# GuardDog.net
KiCad netlist of a schematic drawn in EAGLE
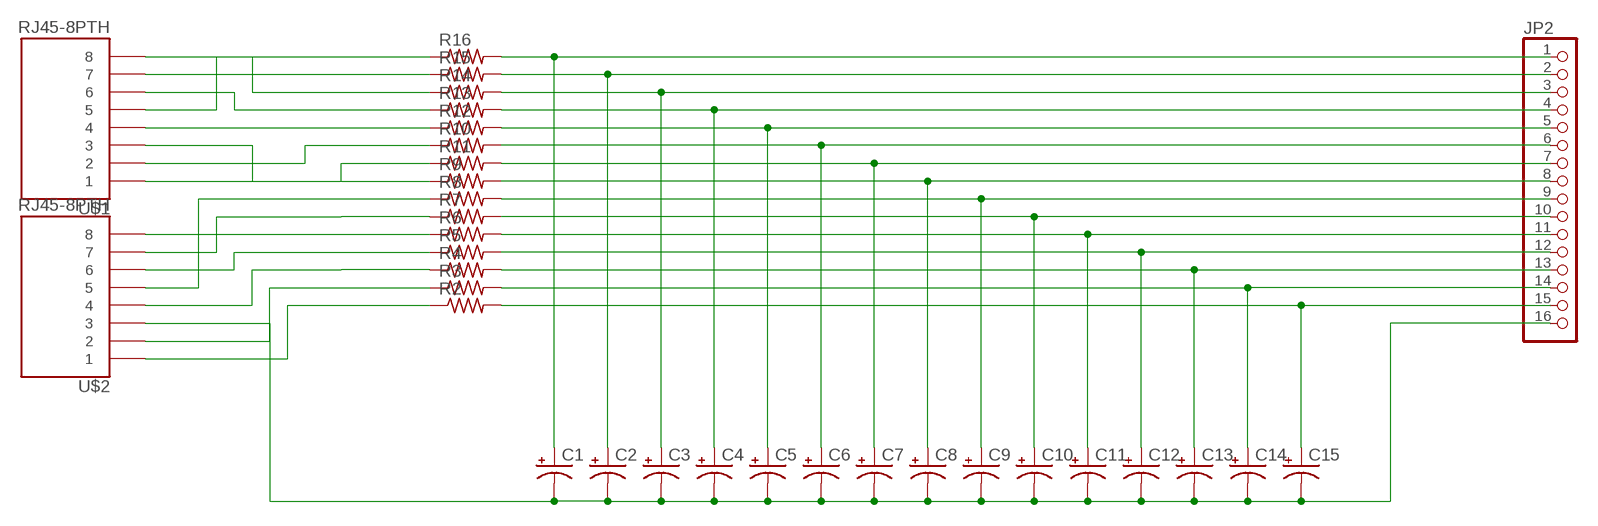
[diagram p0: schematic, sheet 1]

(export (version "E")
  (design (tool "Eeschema 10.0.6"))
  (components
    (comp (ref "C1")
      (value "CAP_POLPTH2")
      (footprint "eagle-import:CPOL-RADIAL-10UF-25V")
      (libsource (lib "eagle-import") (part "CAP_POLPTH2"))
    )
    (comp (ref "C2")
      (value "CAP_POLPTH2")
      (footprint "eagle-import:CPOL-RADIAL-10UF-25V")
      (libsource (lib "eagle-import") (part "CAP_POLPTH2"))
    )
    (comp (ref "C3")
      (value "CAP_POLPTH2")
      (footprint "eagle-import:CPOL-RADIAL-10UF-25V")
      (libsource (lib "eagle-import") (part "CAP_POLPTH2"))
    )
    (comp (ref "C4")
      (value "CAP_POLPTH2")
      (footprint "eagle-import:CPOL-RADIAL-10UF-25V")
      (libsource (lib "eagle-import") (part "CAP_POLPTH2"))
    )
    (comp (ref "C5")
      (value "CAP_POLPTH2")
      (footprint "eagle-import:CPOL-RADIAL-10UF-25V")
      (libsource (lib "eagle-import") (part "CAP_POLPTH2"))
    )
    (comp (ref "C6")
      (value "CAP_POLPTH2")
      (footprint "eagle-import:CPOL-RADIAL-10UF-25V")
      (libsource (lib "eagle-import") (part "CAP_POLPTH2"))
    )
    (comp (ref "C7")
      (value "CAP_POLPTH2")
      (footprint "eagle-import:CPOL-RADIAL-10UF-25V")
      (libsource (lib "eagle-import") (part "CAP_POLPTH2"))
    )
    (comp (ref "C8")
      (value "CAP_POLPTH2")
      (footprint "eagle-import:CPOL-RADIAL-10UF-25V")
      (libsource (lib "eagle-import") (part "CAP_POLPTH2"))
    )
    (comp (ref "C9")
      (value "CAP_POLPTH2")
      (footprint "eagle-import:CPOL-RADIAL-10UF-25V")
      (libsource (lib "eagle-import") (part "CAP_POLPTH2"))
    )
    (comp (ref "C10")
      (value "CAP_POLPTH2")
      (footprint "eagle-import:CPOL-RADIAL-10UF-25V")
      (libsource (lib "eagle-import") (part "CAP_POLPTH2"))
    )
    (comp (ref "C11")
      (value "CAP_POLPTH2")
      (footprint "eagle-import:CPOL-RADIAL-10UF-25V")
      (libsource (lib "eagle-import") (part "CAP_POLPTH2"))
    )
    (comp (ref "C12")
      (value "CAP_POLPTH2")
      (footprint "eagle-import:CPOL-RADIAL-10UF-25V")
      (libsource (lib "eagle-import") (part "CAP_POLPTH2"))
    )
    (comp (ref "C13")
      (value "CAP_POLPTH2")
      (footprint "eagle-import:CPOL-RADIAL-10UF-25V")
      (libsource (lib "eagle-import") (part "CAP_POLPTH2"))
    )
    (comp (ref "C14")
      (value "CAP_POLPTH2")
      (footprint "eagle-import:CPOL-RADIAL-10UF-25V")
      (libsource (lib "eagle-import") (part "CAP_POLPTH2"))
    )
    (comp (ref "C15")
      (value "CAP_POLPTH2")
      (footprint "eagle-import:CPOL-RADIAL-10UF-25V")
      (libsource (lib "eagle-import") (part "CAP_POLPTH2"))
    )
    (comp (ref "JP2")
      (value "PINHD-1X16")
      (footprint "eagle-import:1X16")
      (libsource (lib "eagle-import") (part "PINHD-1X16"))
    )
    (comp (ref "R2")
      (value "R-US_0204/5")
      (footprint "eagle-import:0204_5")
      (libsource (lib "eagle-import") (part "R-US_0204/5"))
    )
    (comp (ref "R3")
      (value "R-US_0204/5")
      (footprint "eagle-import:0204_5")
      (libsource (lib "eagle-import") (part "R-US_0204/5"))
    )
    (comp (ref "R4")
      (value "R-US_0204/5")
      (footprint "eagle-import:0204_5")
      (libsource (lib "eagle-import") (part "R-US_0204/5"))
    )
    (comp (ref "R5")
      (value "R-US_0204/5")
      (footprint "eagle-import:0204_5")
      (libsource (lib "eagle-import") (part "R-US_0204/5"))
    )
    (comp (ref "R6")
      (value "R-US_0204/5")
      (footprint "eagle-import:0204_5")
      (libsource (lib "eagle-import") (part "R-US_0204/5"))
    )
    (comp (ref "R7")
      (value "R-US_0204/5")
      (footprint "eagle-import:0204_5")
      (libsource (lib "eagle-import") (part "R-US_0204/5"))
    )
    (comp (ref "R8")
      (value "R-US_0204/5")
      (footprint "eagle-import:0204_5")
      (libsource (lib "eagle-import") (part "R-US_0204/5"))
    )
    (comp (ref "R9")
      (value "R-US_0204/5")
      (footprint "eagle-import:0204_5")
      (libsource (lib "eagle-import") (part "R-US_0204/5"))
    )
    (comp (ref "R10")
      (value "R-US_0204/5")
      (footprint "eagle-import:0204_5")
      (libsource (lib "eagle-import") (part "R-US_0204/5"))
    )
    (comp (ref "R11")
      (value "R-US_0204/5")
      (footprint "eagle-import:0204_5")
      (libsource (lib "eagle-import") (part "R-US_0204/5"))
    )
    (comp (ref "R12")
      (value "R-US_0204/5")
      (footprint "eagle-import:0204_5")
      (libsource (lib "eagle-import") (part "R-US_0204/5"))
    )
    (comp (ref "R13")
      (value "R-US_0204/5")
      (footprint "eagle-import:0204_5")
      (libsource (lib "eagle-import") (part "R-US_0204/5"))
    )
    (comp (ref "R14")
      (value "R-US_0204/5")
      (footprint "eagle-import:0204_5")
      (libsource (lib "eagle-import") (part "R-US_0204/5"))
    )
    (comp (ref "R15")
      (value "R-US_0204/5")
      (footprint "eagle-import:0204_5")
      (libsource (lib "eagle-import") (part "R-US_0204/5"))
    )
    (comp (ref "R16")
      (value "R-US_0204/5")
      (footprint "eagle-import:0204_5")
      (libsource (lib "eagle-import") (part "R-US_0204/5"))
    )
    (comp (ref "U$1")
      (value "RJ45-8PTH")
      (footprint "eagle-import:RJ45-8")
      (libsource (lib "eagle-import") (part "RJ45-8PTH"))
    )
    (comp (ref "U$2")
      (value "RJ45-8PTH")
      (footprint "eagle-import:RJ45-8")
      (libsource (lib "eagle-import") (part "RJ45-8PTH"))
    )
  )
  (nets
    (net (code "1") (name "Net-(C1-+)") (class "Default")
      (node (ref "C1") (pin "1") (pinfunction "+_1") (pintype "passive"))
      (node (ref "JP2") (pin "1") (pinfunction "1_1") (pintype "passive"))
      (node (ref "R16") (pin "2") (pinfunction "2_2") (pintype "passive"))
    )
    (net (code "2") (name "Net-(C1--)") (class "Default")
      (node (ref "C1") (pin "2") (pinfunction "-_2") (pintype "passive"))
      (node (ref "C10") (pin "2") (pinfunction "-_2") (pintype "passive"))
      (node (ref "C11") (pin "2") (pinfunction "-_2") (pintype "passive"))
      (node (ref "C12") (pin "2") (pinfunction "-_2") (pintype "passive"))
      (node (ref "C13") (pin "2") (pinfunction "-_2") (pintype "passive"))
      (node (ref "C14") (pin "2") (pinfunction "-_2") (pintype "passive"))
      (node (ref "C15") (pin "2") (pinfunction "-_2") (pintype "passive"))
      (node (ref "C2") (pin "2") (pinfunction "-_2") (pintype "passive"))
      (node (ref "C3") (pin "2") (pinfunction "-_2") (pintype "passive"))
      (node (ref "C4") (pin "2") (pinfunction "-_2") (pintype "passive"))
      (node (ref "C5") (pin "2") (pinfunction "-_2") (pintype "passive"))
      (node (ref "C6") (pin "2") (pinfunction "-_2") (pintype "passive"))
      (node (ref "C7") (pin "2") (pinfunction "-_2") (pintype "passive"))
      (node (ref "C8") (pin "2") (pinfunction "-_2") (pintype "passive"))
      (node (ref "C9") (pin "2") (pinfunction "-_2") (pintype "passive"))
      (node (ref "JP2") (pin "16") (pinfunction "16_16") (pintype "passive"))
      (node (ref "U$2") (pin "3") (pinfunction "3_3") (pintype "bidirectional"))
    )
    (net (code "3") (name "Net-(C2-+)") (class "Default")
      (node (ref "C2") (pin "1") (pinfunction "+_1") (pintype "passive"))
      (node (ref "JP2") (pin "2") (pinfunction "2_2") (pintype "passive"))
      (node (ref "R15") (pin "2") (pinfunction "2_2") (pintype "passive"))
    )
    (net (code "4") (name "Net-(C3-+)") (class "Default")
      (node (ref "C3") (pin "1") (pinfunction "+_1") (pintype "passive"))
      (node (ref "JP2") (pin "3") (pinfunction "3_3") (pintype "passive"))
      (node (ref "R14") (pin "2") (pinfunction "2_2") (pintype "passive"))
    )
    (net (code "5") (name "Net-(C4-+)") (class "Default")
      (node (ref "C4") (pin "1") (pinfunction "+_1") (pintype "passive"))
      (node (ref "JP2") (pin "4") (pinfunction "4_4") (pintype "passive"))
      (node (ref "R13") (pin "2") (pinfunction "2_2") (pintype "passive"))
    )
    (net (code "6") (name "Net-(C5-+)") (class "Default")
      (node (ref "C5") (pin "1") (pinfunction "+_1") (pintype "passive"))
      (node (ref "JP2") (pin "5") (pinfunction "5_5") (pintype "passive"))
      (node (ref "R12") (pin "2") (pinfunction "2_2") (pintype "passive"))
    )
    (net (code "7") (name "Net-(C6-+)") (class "Default")
      (node (ref "C6") (pin "1") (pinfunction "+_1") (pintype "passive"))
      (node (ref "JP2") (pin "6") (pinfunction "6_6") (pintype "passive"))
      (node (ref "R10") (pin "2") (pinfunction "2_2") (pintype "passive"))
    )
    (net (code "8") (name "Net-(C7-+)") (class "Default")
      (node (ref "C7") (pin "1") (pinfunction "+_1") (pintype "passive"))
      (node (ref "JP2") (pin "7") (pinfunction "7_7") (pintype "passive"))
      (node (ref "R11") (pin "2") (pinfunction "2_2") (pintype "passive"))
    )
    (net (code "9") (name "Net-(C8-+)") (class "Default")
      (node (ref "C8") (pin "1") (pinfunction "+_1") (pintype "passive"))
      (node (ref "JP2") (pin "8") (pinfunction "8_8") (pintype "passive"))
      (node (ref "R9") (pin "2") (pinfunction "2_2") (pintype "passive"))
    )
    (net (code "10") (name "Net-(C9-+)") (class "Default")
      (node (ref "C9") (pin "1") (pinfunction "+_1") (pintype "passive"))
      (node (ref "JP2") (pin "9") (pinfunction "9_9") (pintype "passive"))
      (node (ref "R8") (pin "2") (pinfunction "2_2") (pintype "passive"))
    )
    (net (code "11") (name "Net-(C10-+)") (class "Default")
      (node (ref "C10") (pin "1") (pinfunction "+_1") (pintype "passive"))
      (node (ref "JP2") (pin "10") (pinfunction "10_10") (pintype "passive"))
      (node (ref "R7") (pin "2") (pinfunction "2_2") (pintype "passive"))
    )
    (net (code "12") (name "Net-(C11-+)") (class "Default")
      (node (ref "C11") (pin "1") (pinfunction "+_1") (pintype "passive"))
      (node (ref "JP2") (pin "11") (pinfunction "11_11") (pintype "passive"))
      (node (ref "R6") (pin "2") (pinfunction "2_2") (pintype "passive"))
    )
    (net (code "13") (name "Net-(C12-+)") (class "Default")
      (node (ref "C12") (pin "1") (pinfunction "+_1") (pintype "passive"))
      (node (ref "JP2") (pin "12") (pinfunction "12_12") (pintype "passive"))
      (node (ref "R5") (pin "2") (pinfunction "2_2") (pintype "passive"))
    )
    (net (code "14") (name "Net-(C13-+)") (class "Default")
      (node (ref "C13") (pin "1") (pinfunction "+_1") (pintype "passive"))
      (node (ref "JP2") (pin "13") (pinfunction "13_13") (pintype "passive"))
      (node (ref "R4") (pin "2") (pinfunction "2_2") (pintype "passive"))
    )
    (net (code "15") (name "Net-(C14-+)") (class "Default")
      (node (ref "C14") (pin "1") (pinfunction "+_1") (pintype "passive"))
      (node (ref "JP2") (pin "14") (pinfunction "14_14") (pintype "passive"))
      (node (ref "R3") (pin "2") (pinfunction "2_2") (pintype "passive"))
    )
    (net (code "16") (name "Net-(C15-+)") (class "Default")
      (node (ref "C15") (pin "1") (pinfunction "+_1") (pintype "passive"))
      (node (ref "JP2") (pin "15") (pinfunction "15_15") (pintype "passive"))
      (node (ref "R2") (pin "2") (pinfunction "2_2") (pintype "passive"))
    )
    (net (code "17") (name "Net-(R2-Pad1)") (class "Default")
      (node (ref "R2") (pin "1") (pinfunction "1_1") (pintype "passive"))
      (node (ref "U$2") (pin "1") (pinfunction "1_1") (pintype "bidirectional"))
    )
    (net (code "18") (name "Net-(R3-Pad1)") (class "Default")
      (node (ref "R3") (pin "1") (pinfunction "1_1") (pintype "passive"))
      (node (ref "U$2") (pin "2") (pinfunction "2_2") (pintype "bidirectional"))
    )
    (net (code "19") (name "Net-(R4-Pad1)") (class "Default")
      (node (ref "R4") (pin "1") (pinfunction "1_1") (pintype "passive"))
      (node (ref "U$2") (pin "4") (pinfunction "4_4") (pintype "bidirectional"))
    )
    (net (code "20") (name "Net-(R5-Pad1)") (class "Default")
      (node (ref "R5") (pin "1") (pinfunction "1_1") (pintype "passive"))
      (node (ref "U$2") (pin "6") (pinfunction "6_6") (pintype "bidirectional"))
    )
    (net (code "21") (name "Net-(R6-Pad1)") (class "Default")
      (node (ref "R6") (pin "1") (pinfunction "1_1") (pintype "passive"))
      (node (ref "U$2") (pin "8") (pinfunction "8_8") (pintype "bidirectional"))
    )
    (net (code "22") (name "Net-(R7-Pad1)") (class "Default")
      (node (ref "R7") (pin "1") (pinfunction "1_1") (pintype "passive"))
      (node (ref "U$2") (pin "7") (pinfunction "7_7") (pintype "bidirectional"))
    )
    (net (code "23") (name "Net-(R8-Pad1)") (class "Default")
      (node (ref "R8") (pin "1") (pinfunction "1_1") (pintype "passive"))
      (node (ref "U$2") (pin "5") (pinfunction "5_5") (pintype "bidirectional"))
    )
    (net (code "24") (name "Net-(R9-Pad1)") (class "Default")
      (node (ref "R9") (pin "1") (pinfunction "1_1") (pintype "passive"))
      (node (ref "U$1") (pin "3") (pinfunction "3_3") (pintype "bidirectional"))
    )
    (net (code "25") (name "Net-(R10-Pad1)") (class "Default")
      (node (ref "R10") (pin "1") (pinfunction "1_1") (pintype "passive"))
      (node (ref "U$1") (pin "2") (pinfunction "2_2") (pintype "bidirectional"))
    )
    (net (code "26") (name "Net-(R11-Pad1)") (class "Default")
      (node (ref "R11") (pin "1") (pinfunction "1_1") (pintype "passive"))
      (node (ref "U$1") (pin "1") (pinfunction "1_1") (pintype "bidirectional"))
    )
    (net (code "27") (name "Net-(R12-Pad1)") (class "Default")
      (node (ref "R12") (pin "1") (pinfunction "1_1") (pintype "passive"))
      (node (ref "U$1") (pin "4") (pinfunction "4_4") (pintype "bidirectional"))
    )
    (net (code "28") (name "Net-(R13-Pad1)") (class "Default")
      (node (ref "R13") (pin "1") (pinfunction "1_1") (pintype "passive"))
      (node (ref "U$1") (pin "6") (pinfunction "6_6") (pintype "bidirectional"))
    )
    (net (code "29") (name "Net-(R14-Pad1)") (class "Default")
      (node (ref "R14") (pin "1") (pinfunction "1_1") (pintype "passive"))
      (node (ref "U$1") (pin "8") (pinfunction "8_8") (pintype "bidirectional"))
    )
    (net (code "30") (name "Net-(R15-Pad1)") (class "Default")
      (node (ref "R15") (pin "1") (pinfunction "1_1") (pintype "passive"))
      (node (ref "U$1") (pin "7") (pinfunction "7_7") (pintype "bidirectional"))
    )
    (net (code "31") (name "Net-(R16-Pad1)") (class "Default")
      (node (ref "R16") (pin "1") (pinfunction "1_1") (pintype "passive"))
      (node (ref "U$1") (pin "5") (pinfunction "5_5") (pintype "bidirectional"))
    )
  )
)
